# main_board.net
KiCad netlist of a schematic drawn in EAGLE
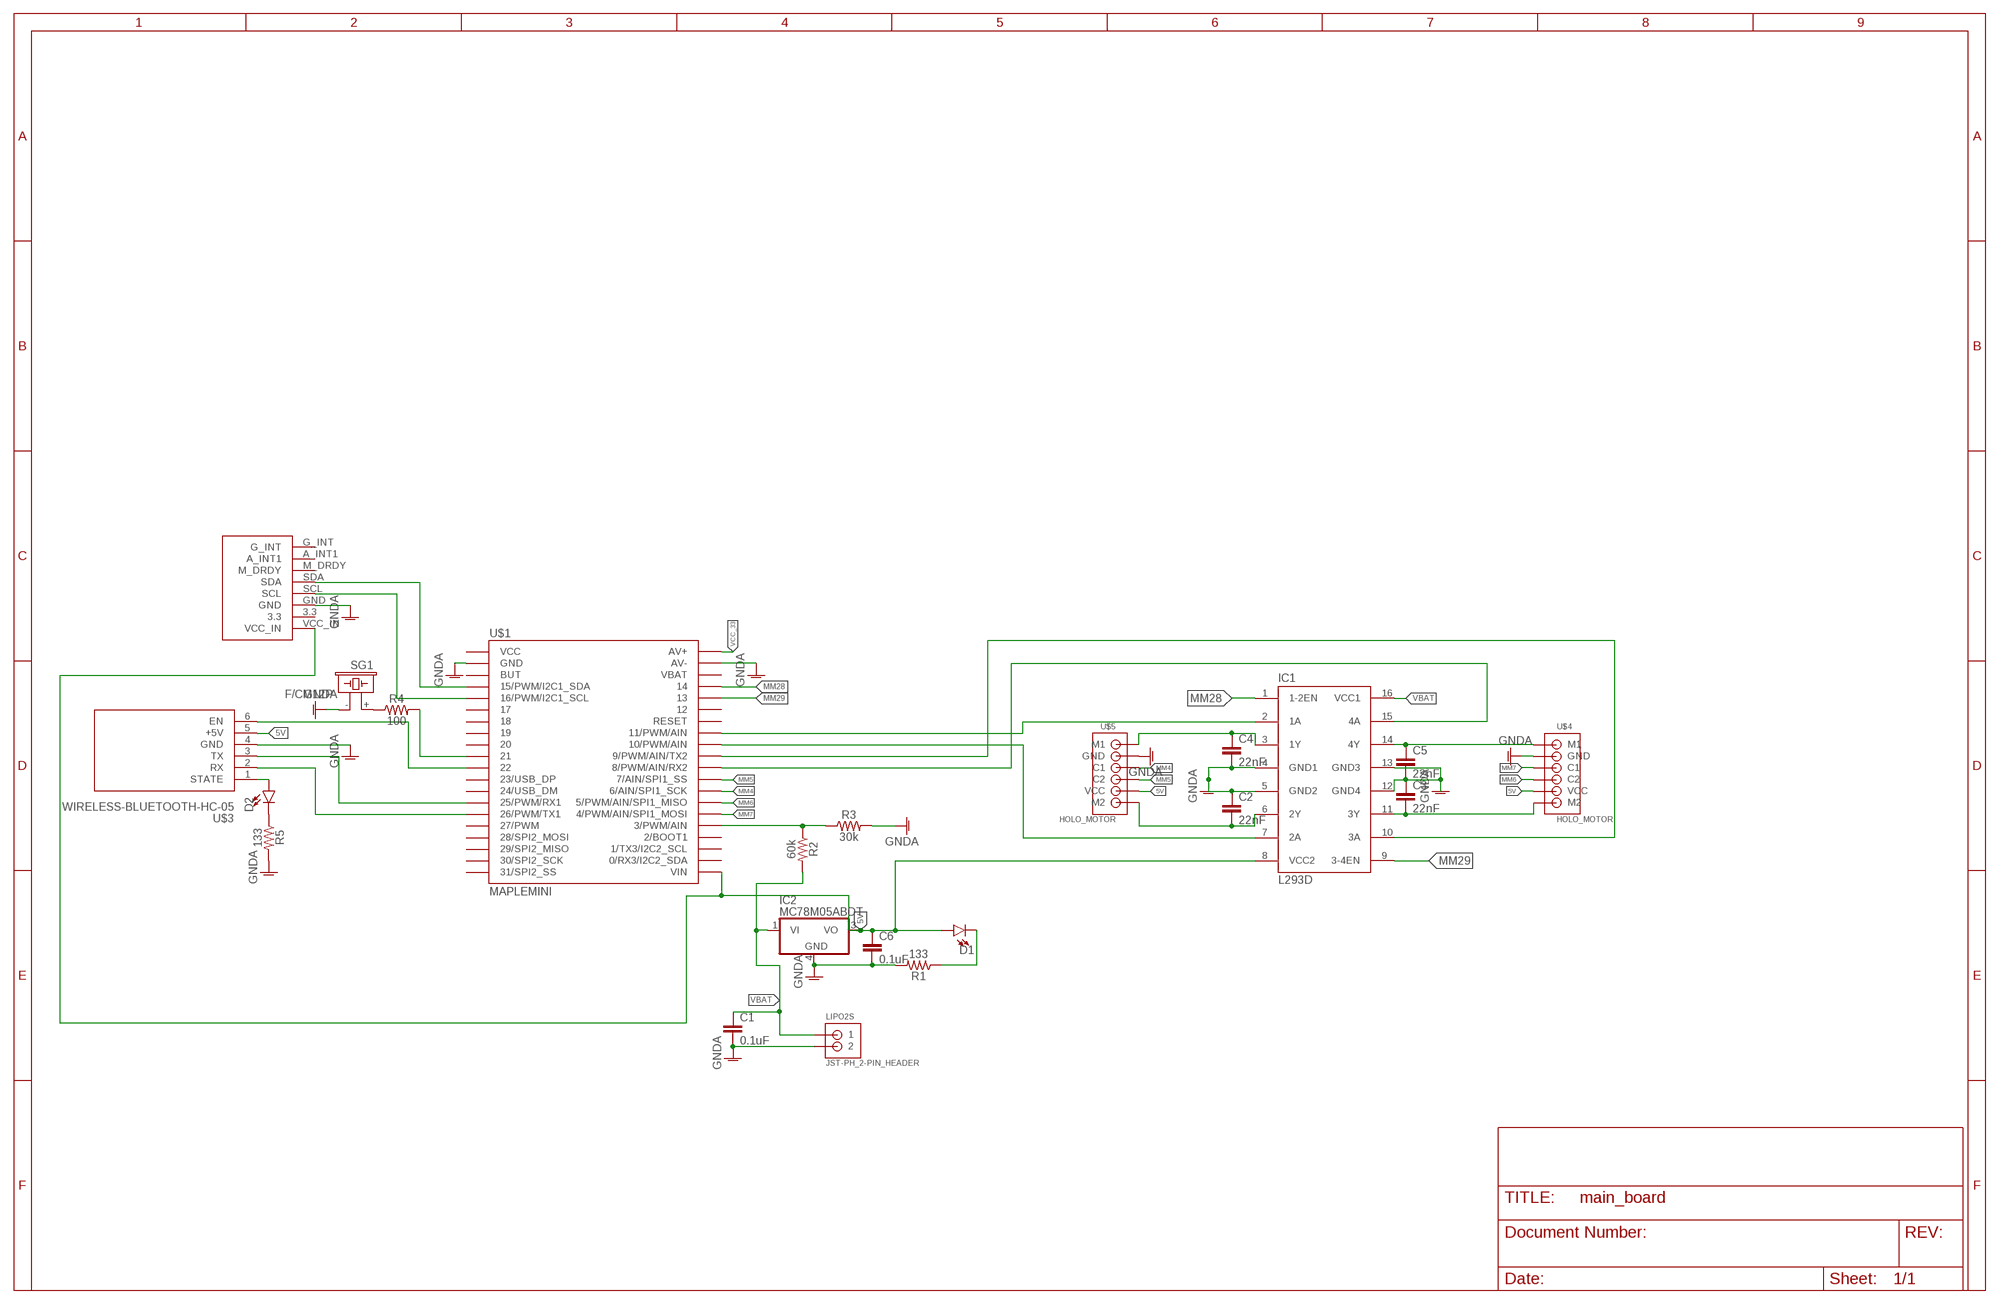
[diagram p0: schematic, sheet 1]

(export (version "E")
  (design (tool "Eeschema 10.0.6"))
  (components
    (comp (ref "C1")
      (value "0.1uF")
      (footprint "eagle-import:0603")
      (libsource (lib "eagle-import") (part "0.1UF-0603-25V-(+80/-20%)"))
    )
    (comp (ref "C2")
      (value "22nF")
      (footprint "eagle-import:0603")
      (libsource (lib "eagle-import") (part "22NF/22,000PF-0603-50V-10%"))
    )
    (comp (ref "C3")
      (value "22nF")
      (footprint "eagle-import:0603")
      (libsource (lib "eagle-import") (part "22NF/22,000PF-0603-50V-10%"))
    )
    (comp (ref "C4")
      (value "22nF")
      (footprint "eagle-import:0603")
      (libsource (lib "eagle-import") (part "22NF/22,000PF-0603-50V-10%"))
    )
    (comp (ref "C5")
      (value "22nF")
      (footprint "eagle-import:0603")
      (libsource (lib "eagle-import") (part "22NF/22,000PF-0603-50V-10%"))
    )
    (comp (ref "C6")
      (value "0.1uF")
      (footprint "eagle-import:0603")
      (libsource (lib "eagle-import") (part "0.1UF-0603-25V-(+80/-20%)"))
    )
    (comp (ref "D1")
      (value "LED-FKIT-1206")
      (footprint "eagle-import:FKIT-LED-1206")
      (libsource (lib "eagle-import") (part "LED-FKIT-1206"))
    )
    (comp (ref "D2")
      (value "LED-FKIT-1206")
      (footprint "eagle-import:FKIT-LED-1206")
      (libsource (lib "eagle-import") (part "LED-FKIT-1206"))
    )
    (comp (ref "IC1")
      (value "L293D")
      (footprint "eagle-import:DIL16")
      (libsource (lib "eagle-import") (part "L293D"))
    )
    (comp (ref "IC2")
      (value "MC78M05ABDT")
      (footprint "eagle-import:DPACK_3")
      (libsource (lib "eagle-import") (part "MC78M05ABDT"))
    )
    (comp (ref "LIPO2S")
      (value "JST-PH_2-PIN_HEADER")
      (footprint "eagle-import:JST_B2B-PH_HEADER")
      (libsource (lib "eagle-import") (part "JST-PH_2-PIN_HEADER"))
    )
    (comp (ref "R1")
      (value "133")
      (footprint "eagle-import:0603")
      (libsource (lib "eagle-import") (part "0.27OHM-0603-1/10W-1%"))
    )
    (comp (ref "R2")
      (value "60k")
      (footprint "eagle-import:0603")
      (libsource (lib "eagle-import") (part "0.27OHM-0603-1/10W-1%"))
    )
    (comp (ref "R3")
      (value "30k")
      (footprint "eagle-import:0603")
      (libsource (lib "eagle-import") (part "0.27OHM-0603-1/10W-1%"))
    )
    (comp (ref "R4")
      (value "100")
      (footprint "eagle-import:0603")
      (libsource (lib "eagle-import") (part "0.27OHM-0603-1/10W-1%"))
    )
    (comp (ref "R5")
      (value "133")
      (footprint "eagle-import:0603")
      (libsource (lib "eagle-import") (part "0.27OHM-0603-1/10W-1%"))
    )
    (comp (ref "SG1")
      (value "F/CM12P")
      (footprint "eagle-import:F_CM12P")
      (libsource (lib "eagle-import") (part "F/CM12P"))
    )
    (comp (ref "U$1")
      (value "MAPLEMINI")
      (footprint "eagle-import:20-DIP")
      (libsource (lib "eagle-import") (part "MAPLEMINI"))
    )
    (comp (ref "U$3")
      (value "WIRELESS-BLUETOOTH-HC-05")
      (footprint "eagle-import:WIRELESS-BLUETOOTH-HC-05")
      (libsource (lib "eagle-import") (part "WIRELESS-BLUETOOTH-HC-05"))
    )
    (comp (ref "U$4")
      (value "HOLO_MOTOR")
      (footprint "eagle-import:HOLO_MOTOR")
      (libsource (lib "eagle-import") (part "HOLO_MOTOR"))
    )
    (comp (ref "U$5")
      (value "HOLO_MOTOR")
      (footprint "eagle-import:HOLO_MOTOR")
      (libsource (lib "eagle-import") (part "HOLO_MOTOR"))
    )
    (comp (ref "U$6")
      (value "GY-85")
      (footprint "eagle-import:GY-85")
      (libsource (lib "eagle-import") (part "GY-85"))
    )
  )
  (nets
    (net (code "1") (name "5V") (class "Default")
      (node (ref "C6") (pin "1") (pinfunction "1_1") (pintype "passive"))
      (node (ref "D1") (pin "A") (pinfunction "A_A") (pintype "passive"))
      (node (ref "IC1") (pin "8") (pinfunction "VCC2_8") (pintype "power_in"))
      (node (ref "IC2") (pin "3") (pinfunction "VO_3") (pintype "passive"))
      (node (ref "U$1") (pin "21") (pinfunction "VIN_21") (pintype "bidirectional"))
      (node (ref "U$3") (pin "5") (pinfunction "+5V_5") (pintype "power_in"))
      (node (ref "U$4") (pin "5") (pinfunction "VCC_5") (pintype "bidirectional"))
      (node (ref "U$5") (pin "5") (pinfunction "VCC_5") (pintype "bidirectional"))
      (node (ref "U$6") (pin "VCC_IN") (pinfunction "VCC_IN_VCC_IN") (pintype "bidirectional"))
    )
    (net (code "2") (name "GNDA") (class "Default")
      (node (ref "C1") (pin "2") (pinfunction "2_2") (pintype "passive"))
      (node (ref "C2") (pin "1") (pinfunction "1_1") (pintype "passive"))
      (node (ref "C3") (pin "1") (pinfunction "1_1") (pintype "passive"))
      (node (ref "C4") (pin "2") (pinfunction "2_2") (pintype "passive"))
      (node (ref "C5") (pin "2") (pinfunction "2_2") (pintype "passive"))
      (node (ref "C6") (pin "2") (pinfunction "2_2") (pintype "passive"))
      (node (ref "IC1") (pin "12") (pinfunction "GND4_12") (pintype "power_in"))
      (node (ref "IC1") (pin "13") (pinfunction "GND3_13") (pintype "power_in"))
      (node (ref "IC1") (pin "4") (pinfunction "GND1_4") (pintype "power_in"))
      (node (ref "IC1") (pin "5") (pinfunction "GND2_5") (pintype "power_in"))
      (node (ref "IC2") (pin "4") (pinfunction "GND_4") (pintype "passive"))
      (node (ref "LIPO2S") (pin "P2") (pinfunction "2_P2") (pintype "bidirectional"))
      (node (ref "R1") (pin "2") (pinfunction "2_2") (pintype "passive"))
      (node (ref "R3") (pin "2") (pinfunction "2_2") (pintype "passive"))
      (node (ref "R5") (pin "2") (pinfunction "2_2") (pintype "passive"))
      (node (ref "SG1") (pin "-") (pinfunction "2_-") (pintype "passive"))
      (node (ref "U$1") (pin "2") (pinfunction "GND_2") (pintype "bidirectional"))
      (node (ref "U$1") (pin "39") (pinfunction "AV-_39") (pintype "bidirectional"))
      (node (ref "U$3") (pin "4") (pinfunction "GND_4") (pintype "power_in"))
      (node (ref "U$4") (pin "2") (pinfunction "GND_2") (pintype "bidirectional"))
      (node (ref "U$5") (pin "2") (pinfunction "GND_2") (pintype "bidirectional"))
      (node (ref "U$6") (pin "GND") (pinfunction "GND_GND") (pintype "bidirectional"))
    )
    (net (code "3") (name "MM4") (class "Default")
      (node (ref "U$1") (pin "28") (pinfunction "6/AIN/SPI1_SCK_28") (pintype "bidirectional"))
      (node (ref "U$5") (pin "3") (pinfunction "C1_3") (pintype "bidirectional"))
    )
    (net (code "4") (name "MM5") (class "Default")
      (node (ref "U$1") (pin "29") (pinfunction "7/AIN/SPI1_SS_29") (pintype "bidirectional"))
      (node (ref "U$5") (pin "4") (pinfunction "C2_4") (pintype "bidirectional"))
    )
    (net (code "5") (name "MM6") (class "Default")
      (node (ref "U$1") (pin "27") (pinfunction "5/PWM/AIN/SPI1_MISO_27") (pintype "bidirectional"))
      (node (ref "U$4") (pin "4") (pinfunction "C2_4") (pintype "bidirectional"))
    )
    (net (code "6") (name "MM7") (class "Default")
      (node (ref "U$1") (pin "26") (pinfunction "4/PWM/AIN/SPI1_MOSI_26") (pintype "bidirectional"))
      (node (ref "U$4") (pin "3") (pinfunction "C1_3") (pintype "bidirectional"))
    )
    (net (code "7") (name "MM28") (class "Default")
      (node (ref "IC1") (pin "1") (pinfunction "1-2EN_1") (pintype "input"))
      (node (ref "U$1") (pin "37") (pinfunction "14_37") (pintype "bidirectional"))
    )
    (net (code "8") (name "MM29") (class "Default")
      (node (ref "IC1") (pin "9") (pinfunction "3-4EN_9") (pintype "input"))
      (node (ref "U$1") (pin "36") (pinfunction "13_36") (pintype "bidirectional"))
    )
    (net (code "9") (name "Net-(D1-PadC)") (class "Default")
      (node (ref "D1") (pin "C") (pinfunction "C_C") (pintype "passive"))
      (node (ref "R1") (pin "1") (pinfunction "1_1") (pintype "passive"))
    )
    (net (code "10") (name "Net-(D2-PadC)") (class "Default")
      (node (ref "D2") (pin "C") (pinfunction "C_C") (pintype "passive"))
      (node (ref "R5") (pin "1") (pinfunction "1_1") (pintype "passive"))
    )
    (net (code "11") (name "Net-(IC1-1A)") (class "Default")
      (node (ref "IC1") (pin "2") (pinfunction "1A_2") (pintype "input"))
      (node (ref "U$1") (pin "33") (pinfunction "11/PWM/AIN_33") (pintype "bidirectional"))
    )
    (net (code "12") (name "Net-(IC1-1Y)") (class "Default")
      (node (ref "C4") (pin "1") (pinfunction "1_1") (pintype "passive"))
      (node (ref "IC1") (pin "3") (pinfunction "1Y_3") (pintype "output"))
      (node (ref "U$5") (pin "1") (pinfunction "M1_1") (pintype "bidirectional"))
    )
    (net (code "13") (name "Net-(IC1-2A)") (class "Default")
      (node (ref "IC1") (pin "7") (pinfunction "2A_7") (pintype "input"))
      (node (ref "U$1") (pin "32") (pinfunction "10/PWM/AIN_32") (pintype "bidirectional"))
    )
    (net (code "14") (name "Net-(IC1-2Y)") (class "Default")
      (node (ref "C2") (pin "2") (pinfunction "2_2") (pintype "passive"))
      (node (ref "IC1") (pin "6") (pinfunction "2Y_6") (pintype "output"))
      (node (ref "U$5") (pin "6") (pinfunction "M2_6") (pintype "bidirectional"))
    )
    (net (code "15") (name "Net-(IC1-3A)") (class "Default")
      (node (ref "IC1") (pin "10") (pinfunction "3A_10") (pintype "input"))
      (node (ref "U$1") (pin "31") (pinfunction "9/PWM/AIN/TX2_31") (pintype "bidirectional"))
    )
    (net (code "16") (name "Net-(IC1-3Y)") (class "Default")
      (node (ref "C3") (pin "2") (pinfunction "2_2") (pintype "passive"))
      (node (ref "IC1") (pin "11") (pinfunction "3Y_11") (pintype "output"))
      (node (ref "U$4") (pin "6") (pinfunction "M2_6") (pintype "bidirectional"))
    )
    (net (code "17") (name "Net-(IC1-4A)") (class "Default")
      (node (ref "IC1") (pin "15") (pinfunction "4A_15") (pintype "input"))
      (node (ref "U$1") (pin "30") (pinfunction "8/PWM/AIN/RX2_30") (pintype "bidirectional"))
    )
    (net (code "18") (name "Net-(IC1-4Y)") (class "Default")
      (node (ref "C5") (pin "1") (pinfunction "1_1") (pintype "passive"))
      (node (ref "IC1") (pin "14") (pinfunction "4Y_14") (pintype "output"))
      (node (ref "U$4") (pin "1") (pinfunction "M1_1") (pintype "bidirectional"))
    )
    (net (code "19") (name "Net-(SG1-1)") (class "Default")
      (node (ref "R4") (pin "1") (pinfunction "1_1") (pintype "passive"))
      (node (ref "SG1") (pin "+") (pinfunction "1_+") (pintype "passive"))
    )
    (net (code "20") (name "Net-(U$1-3{slash}PWM{slash}AIN)") (class "Default")
      (node (ref "R2") (pin "1") (pinfunction "1_1") (pintype "passive"))
      (node (ref "R3") (pin "1") (pinfunction "1_1") (pintype "passive"))
      (node (ref "U$1") (pin "25") (pinfunction "3/PWM/AIN_25") (pintype "bidirectional"))
    )
    (net (code "21") (name "Net-(U$1-15{slash}PWM{slash}I2C1_SDA)") (class "Default")
      (node (ref "U$1") (pin "4") (pinfunction "15/PWM/I2C1_SDA_4") (pintype "bidirectional"))
      (node (ref "U$6") (pin "SDA") (pinfunction "SDA_SDA") (pintype "bidirectional"))
    )
    (net (code "22") (name "Net-(U$1-16{slash}PWM{slash}I2C1_SCL)") (class "Default")
      (node (ref "U$1") (pin "5") (pinfunction "16/PWM/I2C1_SCL_5") (pintype "bidirectional"))
      (node (ref "U$6") (pin "SCL") (pinfunction "SCL_SCL") (pintype "bidirectional"))
    )
    (net (code "23") (name "Net-(U$1-21)") (class "Default")
      (node (ref "R4") (pin "2") (pinfunction "2_2") (pintype "passive"))
      (node (ref "U$1") (pin "10") (pinfunction "21_10") (pintype "bidirectional"))
    )
    (net (code "24") (name "Net-(U$1-22)") (class "Default")
      (node (ref "U$1") (pin "11") (pinfunction "22_11") (pintype "bidirectional"))
      (node (ref "U$3") (pin "6") (pinfunction "EN_6") (pintype "bidirectional"))
    )
    (net (code "25") (name "Net-(U$1-25{slash}PWM{slash}RX1)") (class "Default")
      (node (ref "U$1") (pin "14") (pinfunction "25/PWM/RX1_14") (pintype "bidirectional"))
      (node (ref "U$3") (pin "3") (pinfunction "TX_3") (pintype "bidirectional"))
    )
    (net (code "26") (name "Net-(U$1-26{slash}PWM{slash}TX1)") (class "Default")
      (node (ref "U$1") (pin "15") (pinfunction "26/PWM/TX1_15") (pintype "bidirectional"))
      (node (ref "U$3") (pin "2") (pinfunction "RX_2") (pintype "bidirectional"))
    )
    (net (code "27") (name "Net-(U$3-STATE)") (class "Default")
      (node (ref "D2") (pin "A") (pinfunction "A_A") (pintype "passive"))
      (node (ref "U$3") (pin "1") (pinfunction "STATE_1") (pintype "bidirectional"))
    )
    (net (code "28") (name "VBAT") (class "Default")
      (node (ref "C1") (pin "1") (pinfunction "1_1") (pintype "passive"))
      (node (ref "IC1") (pin "16") (pinfunction "VCC1_16") (pintype "power_in"))
      (node (ref "IC2") (pin "1") (pinfunction "VI_1") (pintype "input"))
      (node (ref "LIPO2S") (pin "P1") (pinfunction "1_P1") (pintype "bidirectional"))
      (node (ref "R2") (pin "2") (pinfunction "2_2") (pintype "passive"))
    )
    (net (code "29") (name "VCC_33") (class "Default")
      (node (ref "U$1") (pin "40") (pinfunction "AV+_40") (pintype "bidirectional"))
    )
    (net (code "30") (name "unconnected-(U$1-0{slash}RX3{slash}I2C2_SDA-Pad22)") (class "Default")
      (node (ref "U$1") (pin "22") (pinfunction "0/RX3/I2C2_SDA_22") (pintype "bidirectional"))
    )
    (net (code "31") (name "unconnected-(U$1-1{slash}TX3{slash}I2C2_SCL-Pad23)") (class "Default")
      (node (ref "U$1") (pin "23") (pinfunction "1/TX3/I2C2_SCL_23") (pintype "bidirectional"))
    )
    (net (code "32") (name "unconnected-(U$1-2{slash}BOOT1-Pad24)") (class "Default")
      (node (ref "U$1") (pin "24") (pinfunction "2/BOOT1_24") (pintype "bidirectional"))
    )
    (net (code "33") (name "unconnected-(U$1-12-Pad35)") (class "Default")
      (node (ref "U$1") (pin "35") (pinfunction "12_35") (pintype "bidirectional"))
    )
    (net (code "34") (name "unconnected-(U$1-17-Pad6)") (class "Default")
      (node (ref "U$1") (pin "6") (pinfunction "17_6") (pintype "bidirectional"))
    )
    (net (code "35") (name "unconnected-(U$1-18-Pad7)") (class "Default")
      (node (ref "U$1") (pin "7") (pinfunction "18_7") (pintype "bidirectional"))
    )
    (net (code "36") (name "unconnected-(U$1-19-Pad8)") (class "Default")
      (node (ref "U$1") (pin "8") (pinfunction "19_8") (pintype "bidirectional"))
    )
    (net (code "37") (name "unconnected-(U$1-20-Pad9)") (class "Default")
      (node (ref "U$1") (pin "9") (pinfunction "20_9") (pintype "bidirectional"))
    )
    (net (code "38") (name "unconnected-(U$1-23{slash}USB_DP-Pad12)") (class "Default")
      (node (ref "U$1") (pin "12") (pinfunction "23/USB_DP_12") (pintype "bidirectional"))
    )
    (net (code "39") (name "unconnected-(U$1-24{slash}USB_DM-Pad13)") (class "Default")
      (node (ref "U$1") (pin "13") (pinfunction "24/USB_DM_13") (pintype "bidirectional"))
    )
    (net (code "40") (name "unconnected-(U$1-27{slash}PWM-Pad16)") (class "Default")
      (node (ref "U$1") (pin "16") (pinfunction "27/PWM_16") (pintype "bidirectional"))
    )
    (net (code "41") (name "unconnected-(U$1-28{slash}SPI2_MOSI-Pad17)") (class "Default")
      (node (ref "U$1") (pin "17") (pinfunction "28/SPI2_MOSI_17") (pintype "bidirectional"))
    )
    (net (code "42") (name "unconnected-(U$1-29{slash}SPI2_MISO-Pad18)") (class "Default")
      (node (ref "U$1") (pin "18") (pinfunction "29/SPI2_MISO_18") (pintype "bidirectional"))
    )
    (net (code "43") (name "unconnected-(U$1-30{slash}SPI2_SCK-Pad19)") (class "Default")
      (node (ref "U$1") (pin "19") (pinfunction "30/SPI2_SCK_19") (pintype "bidirectional"))
    )
    (net (code "44") (name "unconnected-(U$1-31{slash}SPI2_SS-Pad20)") (class "Default")
      (node (ref "U$1") (pin "20") (pinfunction "31/SPI2_SS_20") (pintype "bidirectional"))
    )
    (net (code "45") (name "unconnected-(U$1-BUT-Pad3)") (class "Default")
      (node (ref "U$1") (pin "3") (pinfunction "BUT_3") (pintype "bidirectional"))
    )
    (net (code "46") (name "unconnected-(U$1-RESET-Pad34)") (class "Default")
      (node (ref "U$1") (pin "34") (pinfunction "RESET_34") (pintype "bidirectional"))
    )
    (net (code "47") (name "unconnected-(U$1-VBAT-Pad38)") (class "Default")
      (node (ref "U$1") (pin "38") (pinfunction "VBAT_38") (pintype "bidirectional"))
    )
    (net (code "48") (name "unconnected-(U$1-VCC-Pad1)") (class "Default")
      (node (ref "U$1") (pin "1") (pinfunction "VCC_1") (pintype "bidirectional"))
    )
    (net (code "49") (name "unconnected-(U$6-Pad3.3)") (class "Default")
      (node (ref "U$6") (pin "3.3") (pinfunction "3.3_3.3") (pintype "bidirectional"))
    )
    (net (code "50") (name "unconnected-(U$6-PadA_INT1)") (class "Default")
      (node (ref "U$6") (pin "A_INT1") (pinfunction "A_INT1_A_INT1") (pintype "bidirectional"))
    )
    (net (code "51") (name "unconnected-(U$6-PadG_INT)") (class "Default")
      (node (ref "U$6") (pin "G_INT") (pinfunction "G_INT_G_INT") (pintype "bidirectional"))
    )
    (net (code "52") (name "unconnected-(U$6-PadM_DRDY)") (class "Default")
      (node (ref "U$6") (pin "M_DRDY") (pinfunction "M_DRDY_M_DRDY") (pintype "bidirectional"))
    )
  )
)
